# VALVE_BREAKOUT.net
KiCad netlist of a schematic drawn in EAGLE
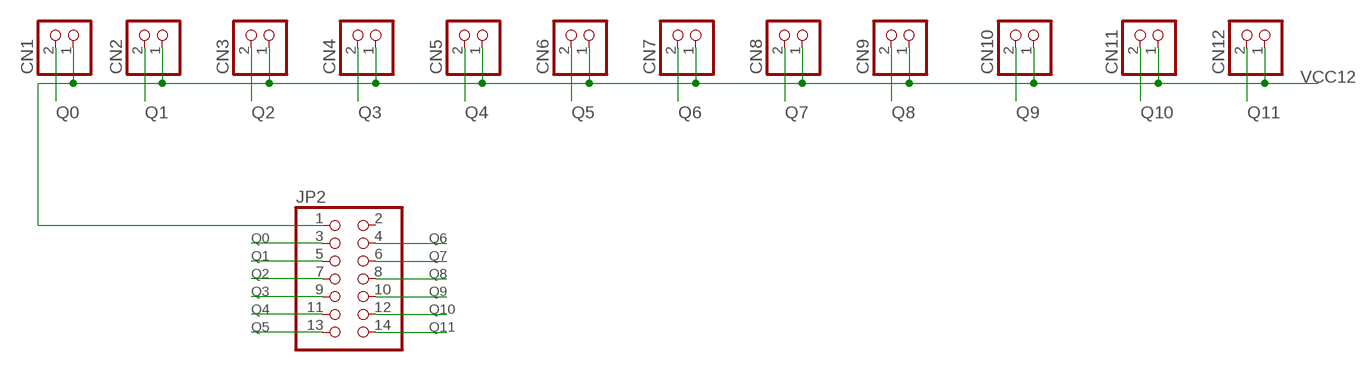
[diagram p0: schematic, sheet 1]

(export (version "E")
  (design (tool "Eeschema 10.0.6"))
  (components
    (comp (ref "CN1")
      (value "JST_2PIN-THM")
      (footprint "eagle-import:JST-PH-2-THM")
      (libsource (lib "eagle-import") (part "JST_2PIN-THM"))
    )
    (comp (ref "CN2")
      (value "JST_2PIN-THM")
      (footprint "eagle-import:JST-PH-2-THM")
      (libsource (lib "eagle-import") (part "JST_2PIN-THM"))
    )
    (comp (ref "CN3")
      (value "JST_2PIN-THM")
      (footprint "eagle-import:JST-PH-2-THM")
      (libsource (lib "eagle-import") (part "JST_2PIN-THM"))
    )
    (comp (ref "CN4")
      (value "JST_2PIN-THM")
      (footprint "eagle-import:JST-PH-2-THM")
      (libsource (lib "eagle-import") (part "JST_2PIN-THM"))
    )
    (comp (ref "CN5")
      (value "JST_2PIN-THM")
      (footprint "eagle-import:JST-PH-2-THM")
      (libsource (lib "eagle-import") (part "JST_2PIN-THM"))
    )
    (comp (ref "CN6")
      (value "JST_2PIN-THM")
      (footprint "eagle-import:JST-PH-2-THM")
      (libsource (lib "eagle-import") (part "JST_2PIN-THM"))
    )
    (comp (ref "CN7")
      (value "JST_2PIN-THM")
      (footprint "eagle-import:JST-PH-2-THM")
      (libsource (lib "eagle-import") (part "JST_2PIN-THM"))
    )
    (comp (ref "CN8")
      (value "JST_2PIN-THM")
      (footprint "eagle-import:JST-PH-2-THM")
      (libsource (lib "eagle-import") (part "JST_2PIN-THM"))
    )
    (comp (ref "CN9")
      (value "JST_2PIN-THM")
      (footprint "eagle-import:JST-PH-2-THM")
      (libsource (lib "eagle-import") (part "JST_2PIN-THM"))
    )
    (comp (ref "CN10")
      (value "JST_2PIN-THM")
      (footprint "eagle-import:JST-PH-2-THM")
      (libsource (lib "eagle-import") (part "JST_2PIN-THM"))
    )
    (comp (ref "CN11")
      (value "JST_2PIN-THM")
      (footprint "eagle-import:JST-PH-2-THM")
      (libsource (lib "eagle-import") (part "JST_2PIN-THM"))
    )
    (comp (ref "CN12")
      (value "JST_2PIN-THM")
      (footprint "eagle-import:JST-PH-2-THM")
      (libsource (lib "eagle-import") (part "JST_2PIN-THM"))
    )
    (comp (ref "JP2")
      (value "PINHD-2X7")
      (footprint "eagle-import:2X07")
      (libsource (lib "eagle-import") (part "PINHD-2X7"))
    )
  )
  (nets
    (net (code "1") (name "/Q0") (class "Default")
      (node (ref "CN1") (pin "2") (pinfunction "1_2") (pintype "passive"))
      (node (ref "JP2") (pin "3") (pinfunction "3_3") (pintype "passive"))
    )
    (net (code "2") (name "/Q1") (class "Default")
      (node (ref "CN2") (pin "2") (pinfunction "1_2") (pintype "passive"))
      (node (ref "JP2") (pin "5") (pinfunction "5_5") (pintype "passive"))
    )
    (net (code "3") (name "/Q2") (class "Default")
      (node (ref "CN3") (pin "2") (pinfunction "1_2") (pintype "passive"))
      (node (ref "JP2") (pin "7") (pinfunction "7_7") (pintype "passive"))
    )
    (net (code "4") (name "/Q3") (class "Default")
      (node (ref "CN4") (pin "2") (pinfunction "1_2") (pintype "passive"))
      (node (ref "JP2") (pin "9") (pinfunction "9_9") (pintype "passive"))
    )
    (net (code "5") (name "/Q4") (class "Default")
      (node (ref "CN5") (pin "2") (pinfunction "1_2") (pintype "passive"))
      (node (ref "JP2") (pin "11") (pinfunction "11_11") (pintype "passive"))
    )
    (net (code "6") (name "/Q5") (class "Default")
      (node (ref "CN6") (pin "2") (pinfunction "1_2") (pintype "passive"))
      (node (ref "JP2") (pin "13") (pinfunction "13_13") (pintype "passive"))
    )
    (net (code "7") (name "/Q6") (class "Default")
      (node (ref "CN7") (pin "2") (pinfunction "1_2") (pintype "passive"))
      (node (ref "JP2") (pin "4") (pinfunction "4_4") (pintype "passive"))
    )
    (net (code "8") (name "/Q7") (class "Default")
      (node (ref "CN8") (pin "2") (pinfunction "1_2") (pintype "passive"))
      (node (ref "JP2") (pin "6") (pinfunction "6_6") (pintype "passive"))
    )
    (net (code "9") (name "/Q8") (class "Default")
      (node (ref "CN9") (pin "2") (pinfunction "1_2") (pintype "passive"))
      (node (ref "JP2") (pin "8") (pinfunction "8_8") (pintype "passive"))
    )
    (net (code "10") (name "/Q9") (class "Default")
      (node (ref "CN10") (pin "2") (pinfunction "1_2") (pintype "passive"))
      (node (ref "JP2") (pin "10") (pinfunction "10_10") (pintype "passive"))
    )
    (net (code "11") (name "/Q10") (class "Default")
      (node (ref "CN11") (pin "2") (pinfunction "1_2") (pintype "passive"))
      (node (ref "JP2") (pin "12") (pinfunction "12_12") (pintype "passive"))
    )
    (net (code "12") (name "/Q11") (class "Default")
      (node (ref "CN12") (pin "2") (pinfunction "1_2") (pintype "passive"))
      (node (ref "JP2") (pin "14") (pinfunction "14_14") (pintype "passive"))
    )
    (net (code "13") (name "/VCC12") (class "Default")
      (node (ref "CN1") (pin "1") (pinfunction "2_1") (pintype "passive"))
      (node (ref "CN10") (pin "1") (pinfunction "2_1") (pintype "passive"))
      (node (ref "CN11") (pin "1") (pinfunction "2_1") (pintype "passive"))
      (node (ref "CN12") (pin "1") (pinfunction "2_1") (pintype "passive"))
      (node (ref "CN2") (pin "1") (pinfunction "2_1") (pintype "passive"))
      (node (ref "CN3") (pin "1") (pinfunction "2_1") (pintype "passive"))
      (node (ref "CN4") (pin "1") (pinfunction "2_1") (pintype "passive"))
      (node (ref "CN5") (pin "1") (pinfunction "2_1") (pintype "passive"))
      (node (ref "CN6") (pin "1") (pinfunction "2_1") (pintype "passive"))
      (node (ref "CN7") (pin "1") (pinfunction "2_1") (pintype "passive"))
      (node (ref "CN8") (pin "1") (pinfunction "2_1") (pintype "passive"))
      (node (ref "CN9") (pin "1") (pinfunction "2_1") (pintype "passive"))
      (node (ref "JP2") (pin "1") (pinfunction "1_1") (pintype "passive"))
    )
    (net (code "14") (name "unconnected-(JP2-Pad2)") (class "Default")
      (node (ref "JP2") (pin "2") (pinfunction "2_2") (pintype "passive"))
    )
  )
)
